# Output_amplifier.net
KiCad netlist of a schematic drawn in Altium Designer
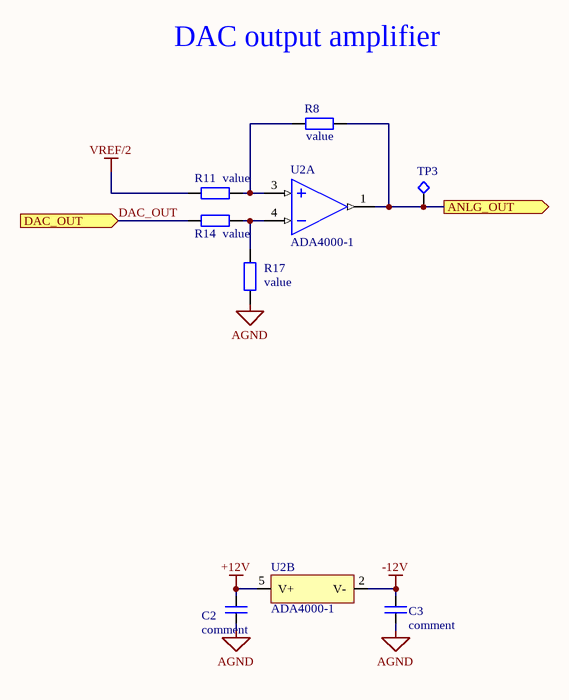
[diagram p0: Output_amplifier.SchDoc]

(export (version "E")
  (design (tool "Eeschema 10.0.6"))
  (components
    (comp (ref "C2")
      (value "comment")
      (footprint "C_0603")
      (description "Generic capacitor")
      (libsource (lib "DAQ") (part "Capacitor"))
    )
    (comp (ref "C3")
      (value "comment")
      (footprint "C_0603")
      (description "Generic capacitor")
      (libsource (lib "DAQ") (part "Capacitor"))
    )
    (comp (ref "R8")
      (value "value")
      (footprint "R_0603")
      (description "Generic resistor")
      (fields (field (name "Comment") "comment"))
      (libsource (lib "DAQ") (part "Resistor"))
    )
    (comp (ref "R11")
      (value "value")
      (footprint "R_0603")
      (description "Generic resistor")
      (fields (field (name "Comment") "comment"))
      (libsource (lib "DAQ") (part "Resistor"))
    )
    (comp (ref "R14")
      (value "value")
      (footprint "R_0603")
      (description "Generic resistor")
      (fields (field (name "Comment") "comment"))
      (libsource (lib "DAQ") (part "Resistor"))
    )
    (comp (ref "R17")
      (value "value")
      (footprint "R_0603")
      (description "Generic resistor")
      (fields (field (name "Comment") "comment"))
      (libsource (lib "DAQ") (part "Resistor"))
    )
    (comp (ref "TP3")
      (value "test point 1.5mm")
      (footprint "TP1_FULL")
      (description "Test point ,1.5mm diameter, no hole")
      (libsource (lib "DAQ") (part "Test Point"))
    )
    (comp (ref "U2")
      (value "ADA4000-1")
      (footprint "SOT23-5")
      (description "Operational Amplifier, Single, 1 Amplifier, 5 MHz, 20 V/µs, ± 4V to ± 18V, TSOT, 5 Pins")
      (fields (field (name "MANUFACTURER") "Analog devices"))
      (libsource (lib "DAQ") (part "ADA4000-1"))
    )
  )
  (nets
    (net (code "1") (name "+12V") (class "Default")
      (node (ref "C2") (pin "1") (pinfunction "1_1") (pintype "passive"))
      (node (ref "U2") (pin "5") (pinfunction "V+_5") (pintype "power_in"))
    )
    (net (code "2") (name "-12V") (class "Default")
      (node (ref "C3") (pin "1") (pinfunction "1_1") (pintype "passive"))
      (node (ref "U2") (pin "2") (pinfunction "V-_2") (pintype "power_in"))
    )
    (net (code "3") (name "/ANLG_OUT") (class "Default")
      (node (ref "R8") (pin "2") (pintype "passive"))
      (node (ref "TP3") (pin "1") (pinfunction "1_1") (pintype "passive"))
      (node (ref "U2") (pin "1") (pinfunction "OUT_1") (pintype "output"))
    )
    (net (code "4") (name "/DAC_OUT") (class "Default") (node (ref "R14") (pin "1") (pintype "passive")))
    (net (code "5") (name "AGND") (class "Default")
      (node (ref "C2") (pin "2") (pinfunction "2_2") (pintype "passive"))
      (node (ref "C3") (pin "2") (pinfunction "2_2") (pintype "passive"))
      (node (ref "R17") (pin "1") (pintype "passive"))
    )
    (net (code "6") (name "Net-(U2A-IN+)") (class "Default")
      (node (ref "R11") (pin "2") (pintype "passive"))
      (node (ref "R8") (pin "1") (pintype "passive"))
      (node (ref "U2") (pin "3") (pinfunction "IN+_3") (pintype "input"))
    )
    (net (code "7") (name "Net-(U2A-IN-)") (class "Default")
      (node (ref "R14") (pin "2") (pintype "passive"))
      (node (ref "R17") (pin "2") (pintype "passive"))
      (node (ref "U2") (pin "4") (pinfunction "IN-_4") (pintype "input"))
    )
    (net (code "8") (name "VREF{slash}2") (class "Default") (node (ref "R11") (pin "1") (pintype "passive")))
  )
)
